# PowerSupply_5V_v2.net
KiCad netlist of a schematic drawn in EAGLE
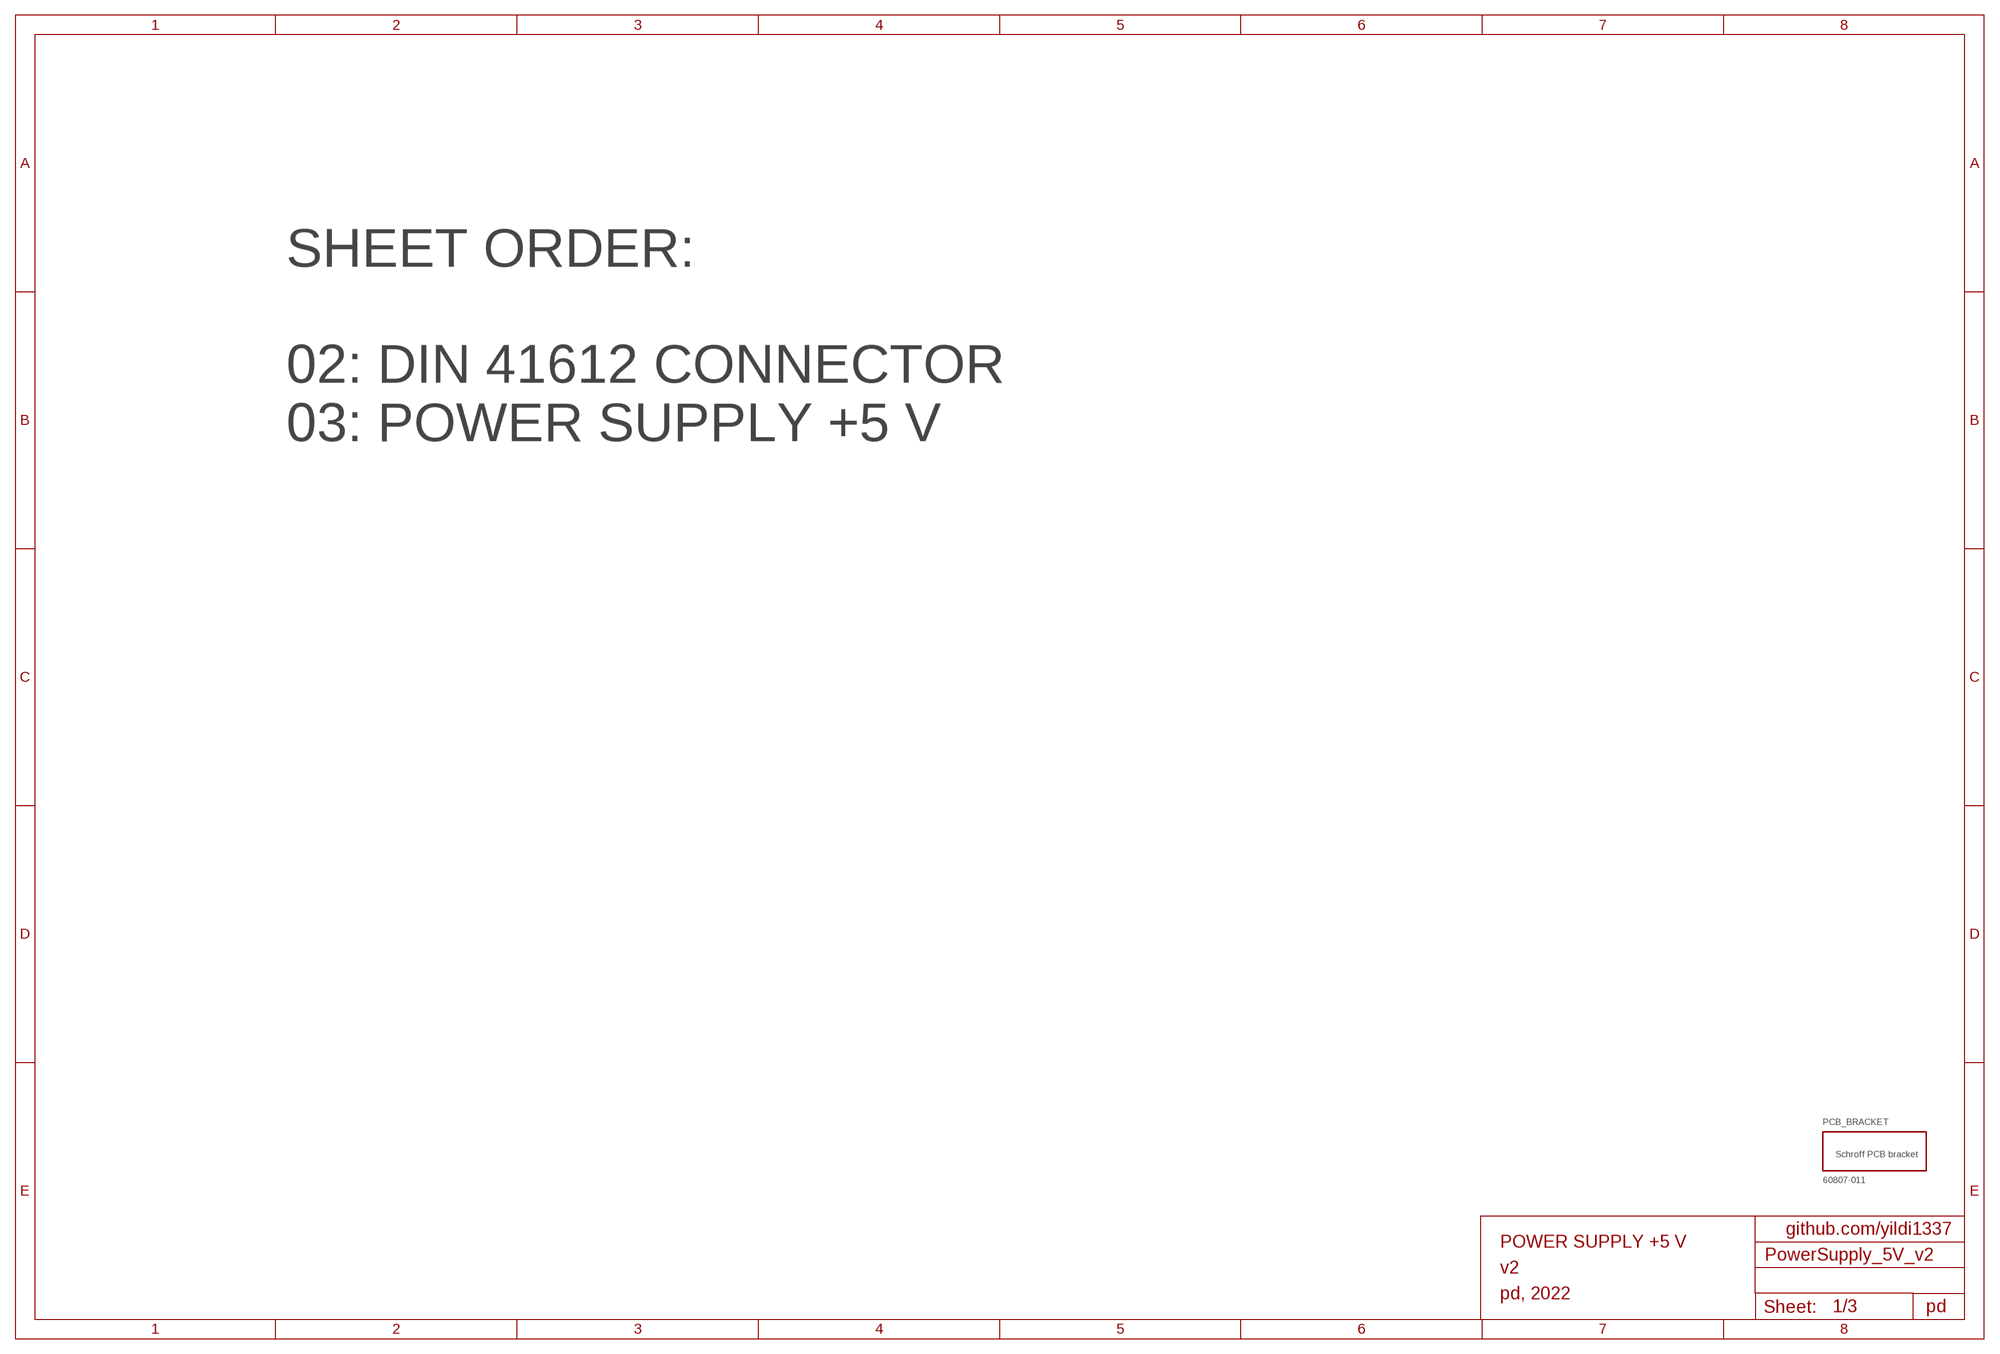
[diagram p0: schematic, sheet 1]
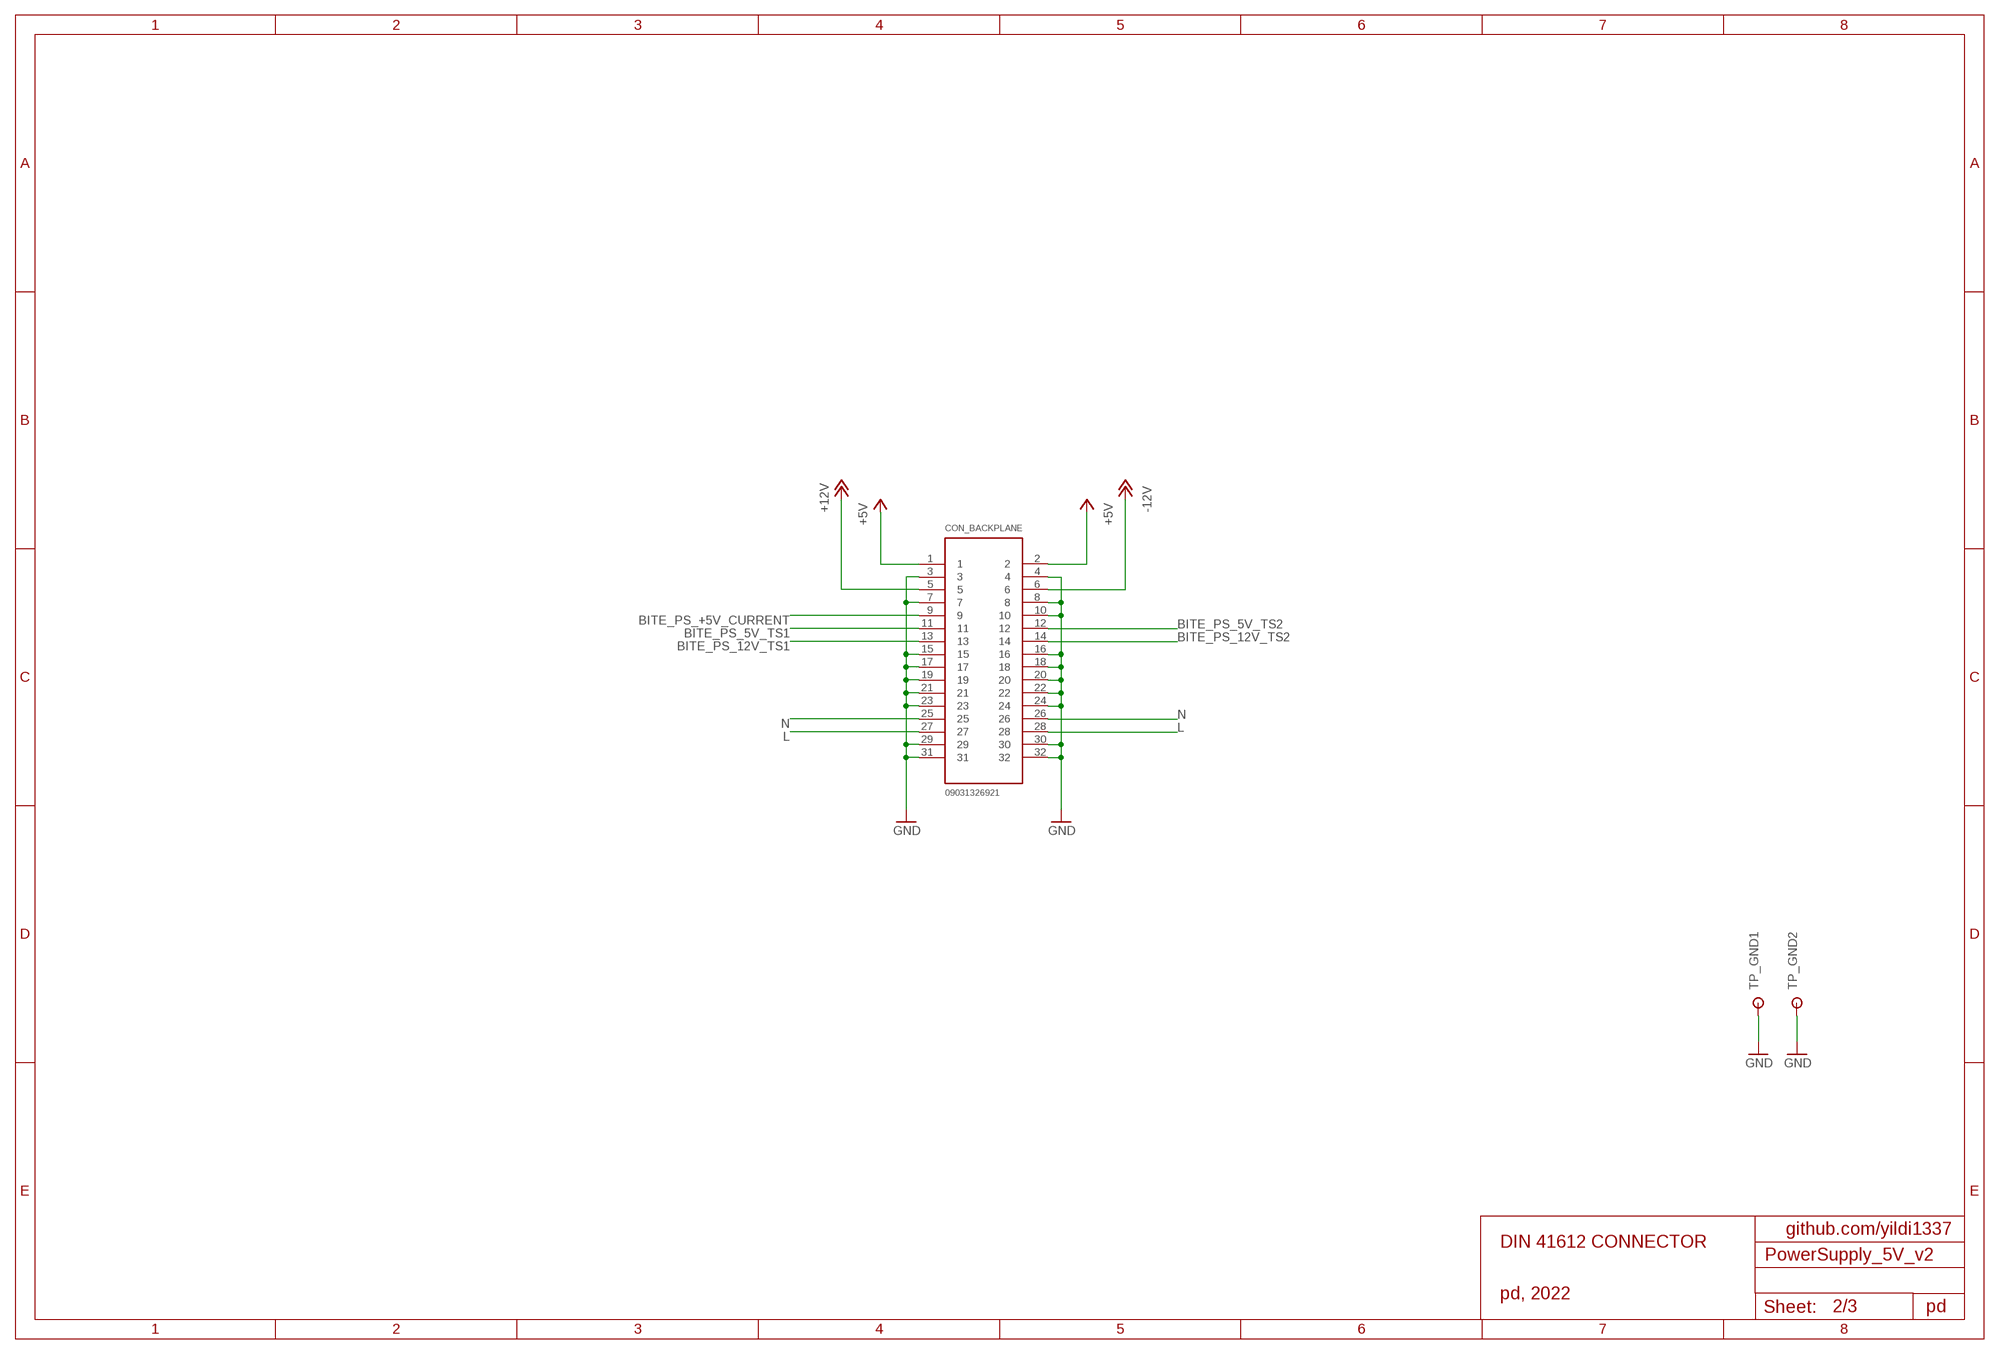
[diagram p1: schematic, sheet 2]
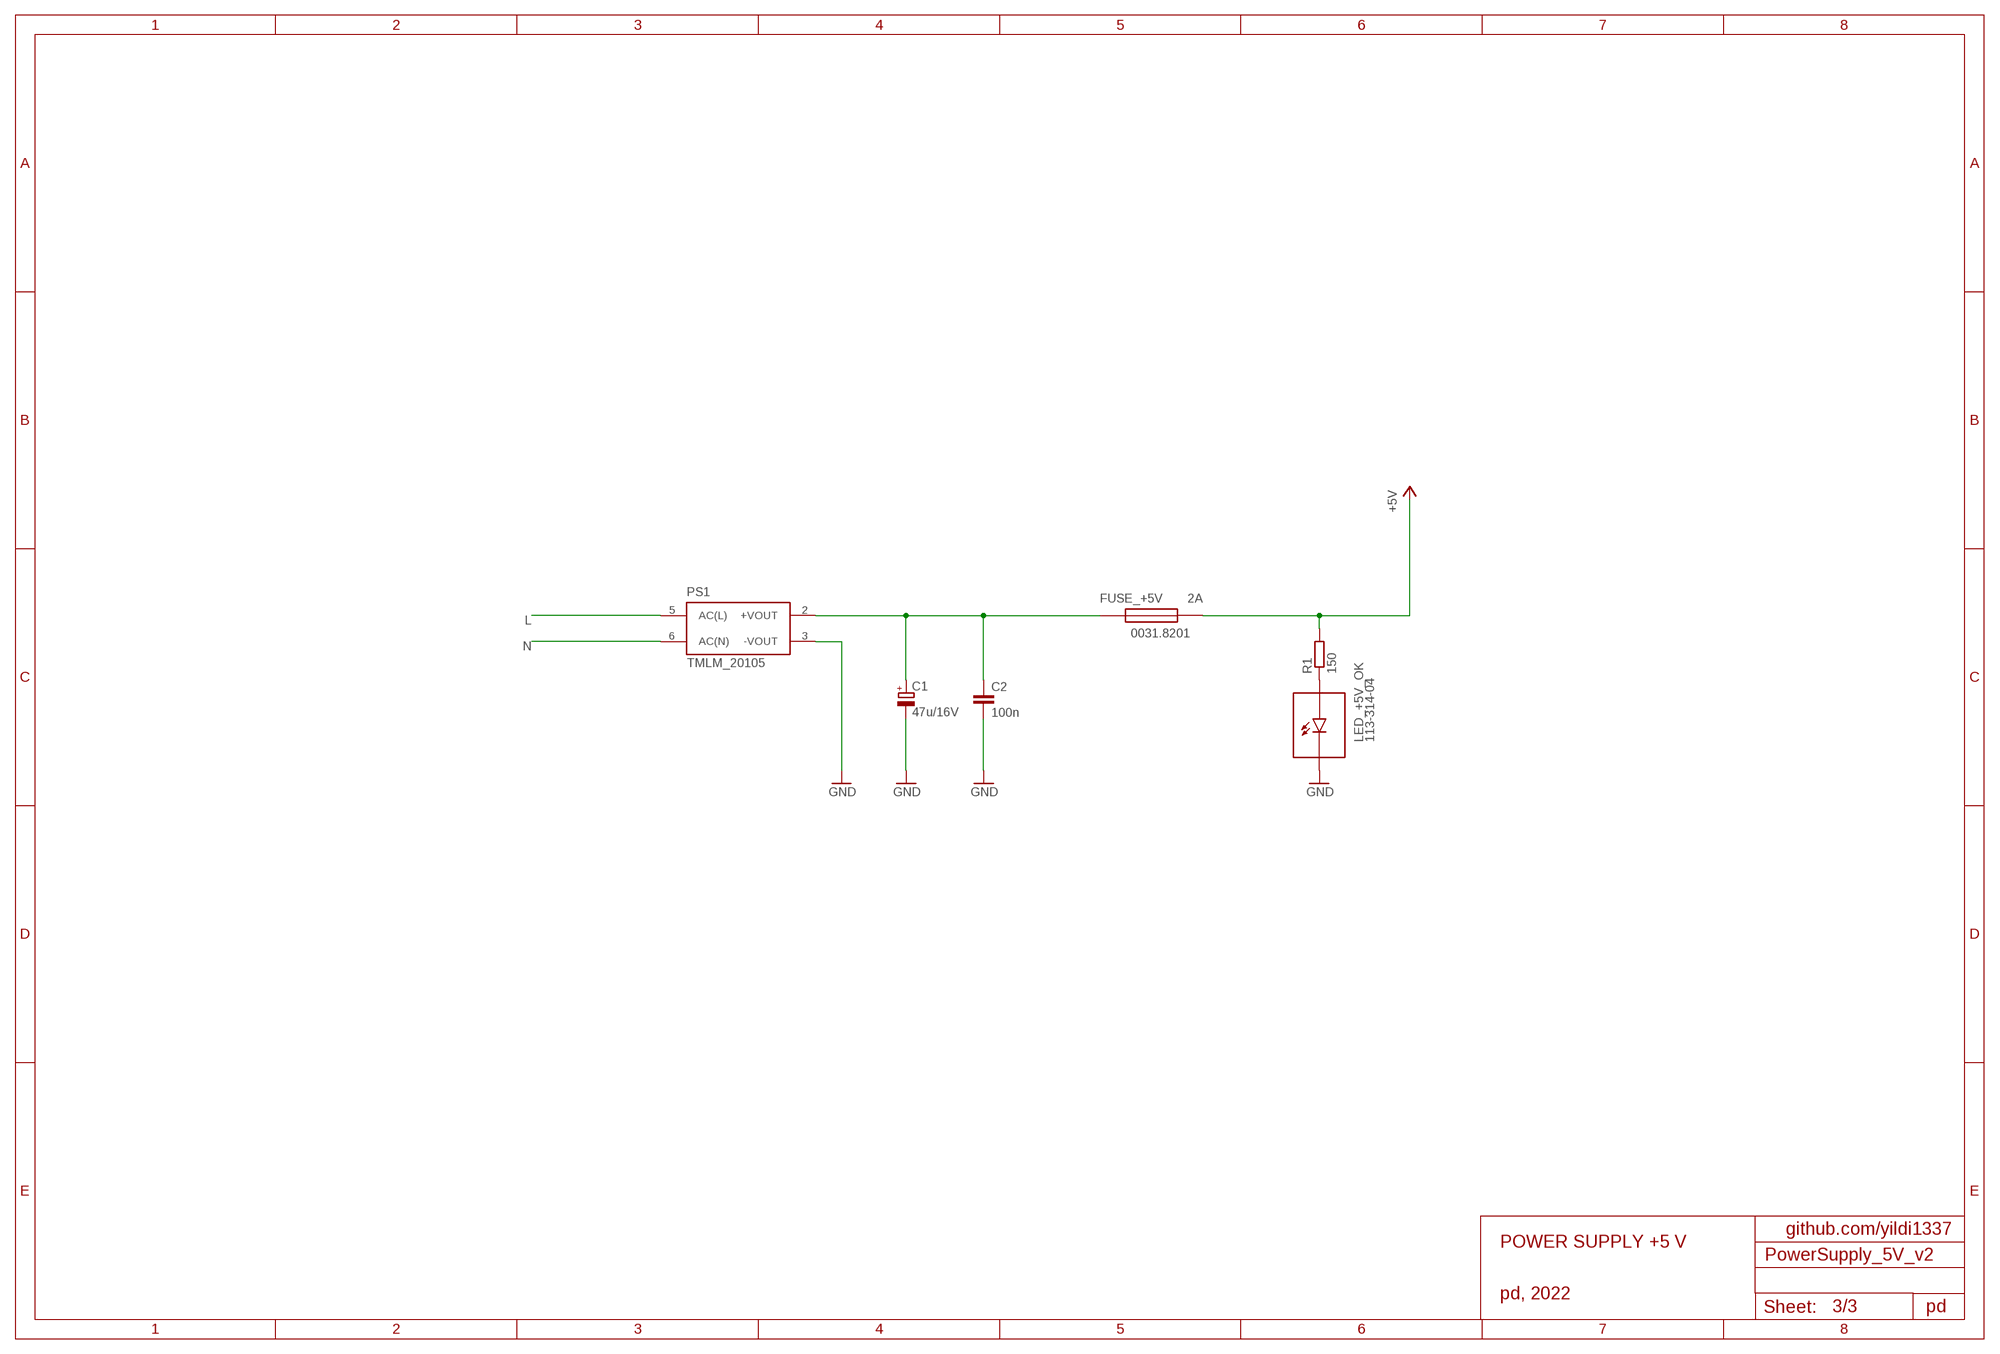
[diagram p2: schematic, sheet 3]

(export (version "E")
  (design (tool "Eeschema 10.0.6"))
  (components
    (comp (ref "CON_BACKPLANE")
      (value "09031326921")
      (footprint "eagle-import:09031326921")
      (libsource (lib "eagle-import") (part "09031326921"))
    )
    (comp (ref "TP_GND1")
      (value "RSPRO-1MM-TERMINAL-POST-2622034")
      (footprint "eagle-import:RSPRO-1MM-TERMINAL-POST-2622034")
      (libsource (lib "eagle-import") (part "RSPRO-1MM-TERMINAL-POST-2622034"))
    )
    (comp (ref "TP_GND2")
      (value "RSPRO-1MM-TERMINAL-POST-2622034")
      (footprint "eagle-import:RSPRO-1MM-TERMINAL-POST-2622034")
      (libsource (lib "eagle-import") (part "RSPRO-1MM-TERMINAL-POST-2622034"))
    )
    (comp (ref "C1")
      (value "47u/16V")
      (footprint "eagle-import:153CLV-0505")
      (libsource (lib "eagle-import") (part "CPOL-EU153CLV-0505"))
    )
    (comp (ref "C2")
      (value "100n")
      (footprint "eagle-import:C0603")
      (libsource (lib "eagle-import") (part "C-EUC0603"))
    )
    (comp (ref "FUSE_+5V")
      (value "0031.8201")
      (footprint "eagle-import:0031.8201")
      (libsource (lib "eagle-import") (part "0031.8201"))
    )
    (comp (ref "LED_+5V_OK")
      (value "113-314-04")
      (footprint "eagle-import:113-314-04")
      (libsource (lib "eagle-import") (part "113-314-04"))
    )
    (comp (ref "PS1")
      (value "TMLM_20105")
      (footprint "eagle-import:TMLM_201XX")
      (libsource (lib "eagle-import") (part "TMLM_201XX"))
    )
    (comp (ref "R1")
      (value "150")
      (footprint "eagle-import:R0603")
      (libsource (lib "eagle-import") (part "R-EU_R0603"))
    )
    (comp (ref "PCB_BRACKET")
      (value "60807-011")
      (footprint "eagle-import:60807-011")
      (libsource (lib "eagle-import") (part "60807-011"))
    )
  )
  (nets
    (net (code "1") (name "+5V") (class "Default")
      (node (ref "CON_BACKPLANE") (pin "1") (pinfunction "1_1") (pintype "bidirectional"))
      (node (ref "CON_BACKPLANE") (pin "2") (pinfunction "2_2") (pintype "bidirectional"))
      (node (ref "FUSE_+5V") (pin "2") (pinfunction "P$2_2") (pintype "bidirectional"))
      (node (ref "R1") (pin "2") (pinfunction "2_2") (pintype "passive"))
    )
    (net (code "2") (name "+12V") (class "Default")
      (node (ref "CON_BACKPLANE") (pin "5") (pinfunction "5_5") (pintype "bidirectional"))
    )
    (net (code "3") (name "-12V") (class "Default")
      (node (ref "CON_BACKPLANE") (pin "6") (pinfunction "6_6") (pintype "bidirectional"))
    )
    (net (code "4") (name "BITE_PS_+5V_CURRENT") (class "Default")
      (node (ref "CON_BACKPLANE") (pin "9") (pinfunction "9_9") (pintype "bidirectional"))
    )
    (net (code "5") (name "BITE_PS_5V_TS1") (class "Default")
      (node (ref "CON_BACKPLANE") (pin "11") (pinfunction "11_11") (pintype "bidirectional"))
    )
    (net (code "6") (name "BITE_PS_5V_TS2") (class "Default")
      (node (ref "CON_BACKPLANE") (pin "12") (pinfunction "12_12") (pintype "bidirectional"))
    )
    (net (code "7") (name "BITE_PS_12V_TS1") (class "Default")
      (node (ref "CON_BACKPLANE") (pin "13") (pinfunction "13_13") (pintype "bidirectional"))
    )
    (net (code "8") (name "BITE_PS_12V_TS2") (class "Default")
      (node (ref "CON_BACKPLANE") (pin "14") (pinfunction "14_14") (pintype "bidirectional"))
    )
    (net (code "9") (name "GND") (class "Default")
      (node (ref "C1") (pin "-") (pinfunction "-_-") (pintype "passive"))
      (node (ref "C2") (pin "2") (pinfunction "2_2") (pintype "passive"))
      (node (ref "CON_BACKPLANE") (pin "10") (pinfunction "10_10") (pintype "bidirectional"))
      (node (ref "CON_BACKPLANE") (pin "15") (pinfunction "15_15") (pintype "bidirectional"))
      (node (ref "CON_BACKPLANE") (pin "16") (pinfunction "16_16") (pintype "bidirectional"))
      (node (ref "CON_BACKPLANE") (pin "17") (pinfunction "17_17") (pintype "bidirectional"))
      (node (ref "CON_BACKPLANE") (pin "18") (pinfunction "18_18") (pintype "bidirectional"))
      (node (ref "CON_BACKPLANE") (pin "19") (pinfunction "19_19") (pintype "bidirectional"))
      (node (ref "CON_BACKPLANE") (pin "20") (pinfunction "20_20") (pintype "bidirectional"))
      (node (ref "CON_BACKPLANE") (pin "21") (pinfunction "21_21") (pintype "bidirectional"))
      (node (ref "CON_BACKPLANE") (pin "22") (pinfunction "22_22") (pintype "bidirectional"))
      (node (ref "CON_BACKPLANE") (pin "23") (pinfunction "23_23") (pintype "bidirectional"))
      (node (ref "CON_BACKPLANE") (pin "24") (pinfunction "24_24") (pintype "bidirectional"))
      (node (ref "CON_BACKPLANE") (pin "29") (pinfunction "29_29") (pintype "bidirectional"))
      (node (ref "CON_BACKPLANE") (pin "3") (pinfunction "3_3") (pintype "bidirectional"))
      (node (ref "CON_BACKPLANE") (pin "30") (pinfunction "30_30") (pintype "bidirectional"))
      (node (ref "CON_BACKPLANE") (pin "31") (pinfunction "31_31") (pintype "bidirectional"))
      (node (ref "CON_BACKPLANE") (pin "32") (pinfunction "32_32") (pintype "bidirectional"))
      (node (ref "CON_BACKPLANE") (pin "4") (pinfunction "4_4") (pintype "bidirectional"))
      (node (ref "CON_BACKPLANE") (pin "7") (pinfunction "7_7") (pintype "bidirectional"))
      (node (ref "CON_BACKPLANE") (pin "8") (pinfunction "8_8") (pintype "bidirectional"))
      (node (ref "LED_+5V_OK") (pin "-") (pinfunction "C_-") (pintype "passive"))
      (node (ref "PS1") (pin "3") (pinfunction "-VOUT_3") (pintype "output"))
      (node (ref "TP_GND1") (pin "P$1") (pinfunction "P$1_P$1") (pintype "bidirectional"))
      (node (ref "TP_GND2") (pin "P$1") (pinfunction "P$1_P$1") (pintype "bidirectional"))
    )
    (net (code "10") (name "L") (class "Default")
      (node (ref "CON_BACKPLANE") (pin "27") (pinfunction "27_27") (pintype "bidirectional"))
      (node (ref "CON_BACKPLANE") (pin "28") (pinfunction "28_28") (pintype "bidirectional"))
      (node (ref "PS1") (pin "5") (pinfunction "AC(L)_5") (pintype "input"))
    )
    (net (code "11") (name "N") (class "Default")
      (node (ref "CON_BACKPLANE") (pin "25") (pinfunction "25_25") (pintype "bidirectional"))
      (node (ref "CON_BACKPLANE") (pin "26") (pinfunction "26_26") (pintype "bidirectional"))
      (node (ref "PS1") (pin "6") (pinfunction "AC(N)_6") (pintype "input"))
    )
    (net (code "12") (name "Net-(FUSE_+5V-P$1)") (class "Default")
      (node (ref "C1") (pin "+") (pinfunction "+_+") (pintype "passive"))
      (node (ref "C2") (pin "1") (pinfunction "1_1") (pintype "passive"))
      (node (ref "FUSE_+5V") (pin "1") (pinfunction "P$1_1") (pintype "bidirectional"))
      (node (ref "PS1") (pin "2") (pinfunction "+VOUT_2") (pintype "output"))
    )
    (net (code "13") (name "Net-(LED_+5V_OK-A)") (class "Default")
      (node (ref "LED_+5V_OK") (pin "+") (pinfunction "A_+") (pintype "passive"))
      (node (ref "R1") (pin "1") (pinfunction "1_1") (pintype "passive"))
    )
  )
)
